# V_1.net
KiCad netlist of a schematic drawn in Altium Designer
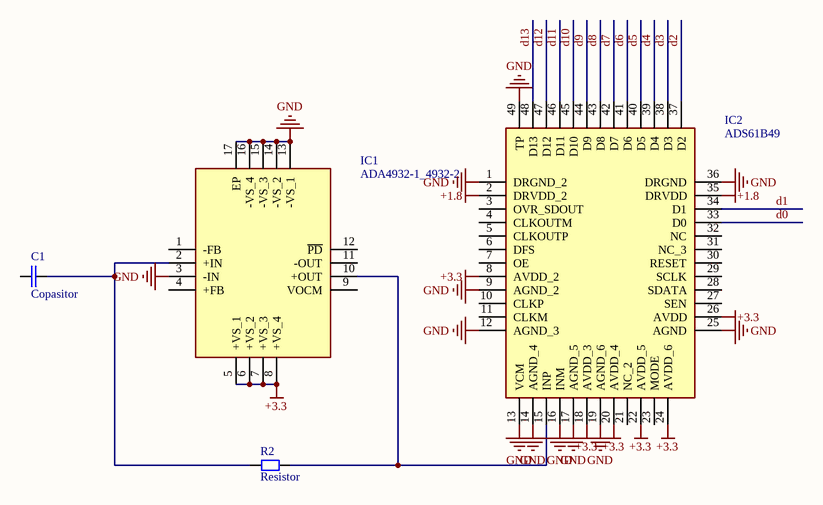
[diagram p0: V_1.SchDoc]

(export (version "E")
  (design (tool "Eeschema 10.0.6"))
  (components
    (comp (ref "C1") (value "Copasitor") (footprint "Copasitor") (libsource (lib "V_1") (part "Copasitor")))
    (comp (ref "IC1")
      (value "ADA4932-1_4932-2")
      (footprint "ADA4932-1")
      (libsource (lib "V_1") (part "ADA4932-1_4932-2"))
    )
    (comp (ref "IC2") (value "ADS61B49") (footprint "ADS61b49") (libsource (lib "V_1") (part "ADS61B49")))
    (comp (ref "R2") (value "Resistor") (footprint "Resistor") (libsource (lib "V_1") (part "Resistor")))
  )
  (nets
    (net (code "1") (name "+1.8") (class "Default")
      (node (ref "IC2") (pin "2") (pinfunction "DRVDD_2_2") (pintype "passive"))
      (node (ref "IC2") (pin "35") (pinfunction "DRVDD_35") (pintype "passive"))
    )
    (net (code "2") (name "+3.3") (class "Default")
      (node (ref "IC1") (pin "5") (pinfunction "+VS_1_5") (pintype "passive"))
      (node (ref "IC1") (pin "6") (pinfunction "+VS_2_6") (pintype "passive"))
      (node (ref "IC1") (pin "7") (pinfunction "+VS_3_7") (pintype "passive"))
      (node (ref "IC1") (pin "8") (pinfunction "+VS_4_8") (pintype "passive"))
      (node (ref "IC2") (pin "18") (pinfunction "AVDD_3_18") (pintype "passive"))
      (node (ref "IC2") (pin "20") (pinfunction "AVDD_4_20") (pintype "passive"))
      (node (ref "IC2") (pin "22") (pinfunction "AVDD_5_22") (pintype "passive"))
      (node (ref "IC2") (pin "24") (pinfunction "AVDD_6_24") (pintype "passive"))
      (node (ref "IC2") (pin "26") (pinfunction "AVDD_26") (pintype "passive"))
      (node (ref "IC2") (pin "8") (pinfunction "AVDD_2_8") (pintype "passive"))
    )
    (net (code "3") (name "/d0") (class "Default")
      (node (ref "IC2") (pin "33") (pinfunction "D0_33") (pintype "passive"))
    )
    (net (code "4") (name "/d1") (class "Default")
      (node (ref "IC2") (pin "34") (pinfunction "D1_34") (pintype "passive"))
    )
    (net (code "5") (name "/d2") (class "Default")
      (node (ref "IC2") (pin "37") (pinfunction "D2_37") (pintype "passive"))
    )
    (net (code "6") (name "/d3") (class "Default")
      (node (ref "IC2") (pin "38") (pinfunction "D3_38") (pintype "passive"))
    )
    (net (code "7") (name "/d4") (class "Default")
      (node (ref "IC2") (pin "39") (pinfunction "D4_39") (pintype "passive"))
    )
    (net (code "8") (name "/d5") (class "Default")
      (node (ref "IC2") (pin "40") (pinfunction "D5_40") (pintype "passive"))
    )
    (net (code "9") (name "/d6") (class "Default")
      (node (ref "IC2") (pin "41") (pinfunction "D6_41") (pintype "passive"))
    )
    (net (code "10") (name "/d7") (class "Default")
      (node (ref "IC2") (pin "42") (pinfunction "D7_42") (pintype "passive"))
    )
    (net (code "11") (name "/d8") (class "Default")
      (node (ref "IC2") (pin "43") (pinfunction "D8_43") (pintype "passive"))
    )
    (net (code "12") (name "/d9") (class "Default")
      (node (ref "IC2") (pin "44") (pinfunction "D9_44") (pintype "passive"))
    )
    (net (code "13") (name "/d10") (class "Default")
      (node (ref "IC2") (pin "45") (pinfunction "D10_45") (pintype "passive"))
    )
    (net (code "14") (name "/d11") (class "Default")
      (node (ref "IC2") (pin "46") (pinfunction "D11_46") (pintype "passive"))
    )
    (net (code "15") (name "/d12") (class "Default")
      (node (ref "IC2") (pin "47") (pinfunction "D12_47") (pintype "passive"))
    )
    (net (code "16") (name "/d13") (class "Default")
      (node (ref "IC2") (pin "48") (pinfunction "D13_48") (pintype "passive"))
    )
    (net (code "17") (name "GND") (class "Default")
      (node (ref "IC1") (pin "13") (pinfunction "-VS_1_13") (pintype "passive"))
      (node (ref "IC1") (pin "14") (pinfunction "-VS_2_14") (pintype "passive"))
      (node (ref "IC1") (pin "15") (pinfunction "-VS_3_15") (pintype "passive"))
      (node (ref "IC1") (pin "16") (pinfunction "-VS_4_16") (pintype "passive"))
      (node (ref "IC1") (pin "17") (pinfunction "EP_17") (pintype "passive"))
      (node (ref "IC1") (pin "3") (pinfunction "-IN_3") (pintype "passive"))
      (node (ref "IC2") (pin "1") (pinfunction "DRGND_2_1") (pintype "passive"))
      (node (ref "IC2") (pin "12") (pinfunction "AGND_3_12") (pintype "passive"))
      (node (ref "IC2") (pin "13") (pinfunction "VCM_13") (pintype "passive"))
      (node (ref "IC2") (pin "14") (pinfunction "AGND_4_14") (pintype "passive"))
      (node (ref "IC2") (pin "16") (pinfunction "INM_16") (pintype "passive"))
      (node (ref "IC2") (pin "17") (pinfunction "AGND_5_17") (pintype "passive"))
      (node (ref "IC2") (pin "19") (pinfunction "AGND_6_19") (pintype "passive"))
      (node (ref "IC2") (pin "25") (pinfunction "AGND_25") (pintype "passive"))
      (node (ref "IC2") (pin "36") (pinfunction "DRGND_36") (pintype "passive"))
      (node (ref "IC2") (pin "49") (pinfunction "TP_49") (pintype "passive"))
      (node (ref "IC2") (pin "9") (pinfunction "AGND_2_9") (pintype "passive"))
    )
    (net (code "18") (name "Net-(IC1-+IN)") (class "Default")
      (node (ref "C1") (pin "2") (pintype "passive"))
      (node (ref "IC1") (pin "2") (pinfunction "+IN_2") (pintype "passive"))
      (node (ref "R2") (pin "1") (pintype "passive"))
    )
    (net (code "19") (name "Net-(IC1-+OUT)") (class "Default")
      (node (ref "IC1") (pin "10") (pinfunction "+OUT_10") (pintype "passive"))
      (node (ref "IC2") (pin "15") (pinfunction "INP_15") (pintype "passive"))
      (node (ref "R2") (pin "2") (pintype "passive"))
    )
    (net (code "20") (name "unconnected-(C1-Pad1)") (class "Default")
      (node (ref "C1") (pin "1") (pintype "passive"))
    )
    (net (code "21") (name "unconnected-(IC1-+FB-Pad4)") (class "Default")
      (node (ref "IC1") (pin "4") (pinfunction "+FB_4") (pintype "passive"))
    )
    (net (code "22") (name "unconnected-(IC1--FB-Pad1)") (class "Default")
      (node (ref "IC1") (pin "1") (pinfunction "-FB_1") (pintype "passive"))
    )
    (net (code "23") (name "unconnected-(IC1--OUT-Pad11)") (class "Default")
      (node (ref "IC1") (pin "11") (pinfunction "-OUT_11") (pintype "passive"))
    )
    (net (code "24") (name "unconnected-(IC1-VOCM-Pad9)") (class "Default")
      (node (ref "IC1") (pin "9") (pinfunction "VOCM_9") (pintype "passive"))
    )
    (net (code "25") (name "unconnected-(IC1-~{PD}-Pad12)") (class "Default")
      (node (ref "IC1") (pin "12") (pinfunction "~{PD}_12") (pintype "passive"))
    )
    (net (code "26") (name "unconnected-(IC2-CLKM-Pad11)") (class "Default")
      (node (ref "IC2") (pin "11") (pinfunction "CLKM_11") (pintype "passive"))
    )
    (net (code "27") (name "unconnected-(IC2-CLKOUTM-Pad4)") (class "Default")
      (node (ref "IC2") (pin "4") (pinfunction "CLKOUTM_4") (pintype "passive"))
    )
    (net (code "28") (name "unconnected-(IC2-CLKOUTP-Pad5)") (class "Default")
      (node (ref "IC2") (pin "5") (pinfunction "CLKOUTP_5") (pintype "passive"))
    )
    (net (code "29") (name "unconnected-(IC2-CLKP-Pad10)") (class "Default")
      (node (ref "IC2") (pin "10") (pinfunction "CLKP_10") (pintype "passive"))
    )
    (net (code "30") (name "unconnected-(IC2-DFS-Pad6)") (class "Default")
      (node (ref "IC2") (pin "6") (pinfunction "DFS_6") (pintype "passive"))
    )
    (net (code "31") (name "unconnected-(IC2-MODE-Pad23)") (class "Default")
      (node (ref "IC2") (pin "23") (pinfunction "MODE_23") (pintype "passive"))
    )
    (net (code "32") (name "unconnected-(IC2-NC-Pad32)") (class "Default")
      (node (ref "IC2") (pin "32") (pinfunction "NC_32") (pintype "passive"))
    )
    (net (code "33") (name "unconnected-(IC2-NC_2-Pad21)") (class "Default")
      (node (ref "IC2") (pin "21") (pinfunction "NC_2_21") (pintype "passive"))
    )
    (net (code "34") (name "unconnected-(IC2-NC_3-Pad31)") (class "Default")
      (node (ref "IC2") (pin "31") (pinfunction "NC_3_31") (pintype "passive"))
    )
    (net (code "35") (name "unconnected-(IC2-OE-Pad7)") (class "Default")
      (node (ref "IC2") (pin "7") (pinfunction "OE_7") (pintype "passive"))
    )
    (net (code "36") (name "unconnected-(IC2-OVR_SDOUT-Pad3)") (class "Default")
      (node (ref "IC2") (pin "3") (pinfunction "OVR_SDOUT_3") (pintype "passive"))
    )
    (net (code "37") (name "unconnected-(IC2-RESET-Pad30)") (class "Default")
      (node (ref "IC2") (pin "30") (pinfunction "RESET_30") (pintype "passive"))
    )
    (net (code "38") (name "unconnected-(IC2-SCLK-Pad29)") (class "Default")
      (node (ref "IC2") (pin "29") (pinfunction "SCLK_29") (pintype "passive"))
    )
    (net (code "39") (name "unconnected-(IC2-SDATA-Pad28)") (class "Default")
      (node (ref "IC2") (pin "28") (pinfunction "SDATA_28") (pintype "passive"))
    )
    (net (code "40") (name "unconnected-(IC2-SEN-Pad27)") (class "Default")
      (node (ref "IC2") (pin "27") (pinfunction "SEN_27") (pintype "passive"))
    )
  )
)
